# sch_Power.net
KiCad netlist of a schematic drawn in Altium Designer
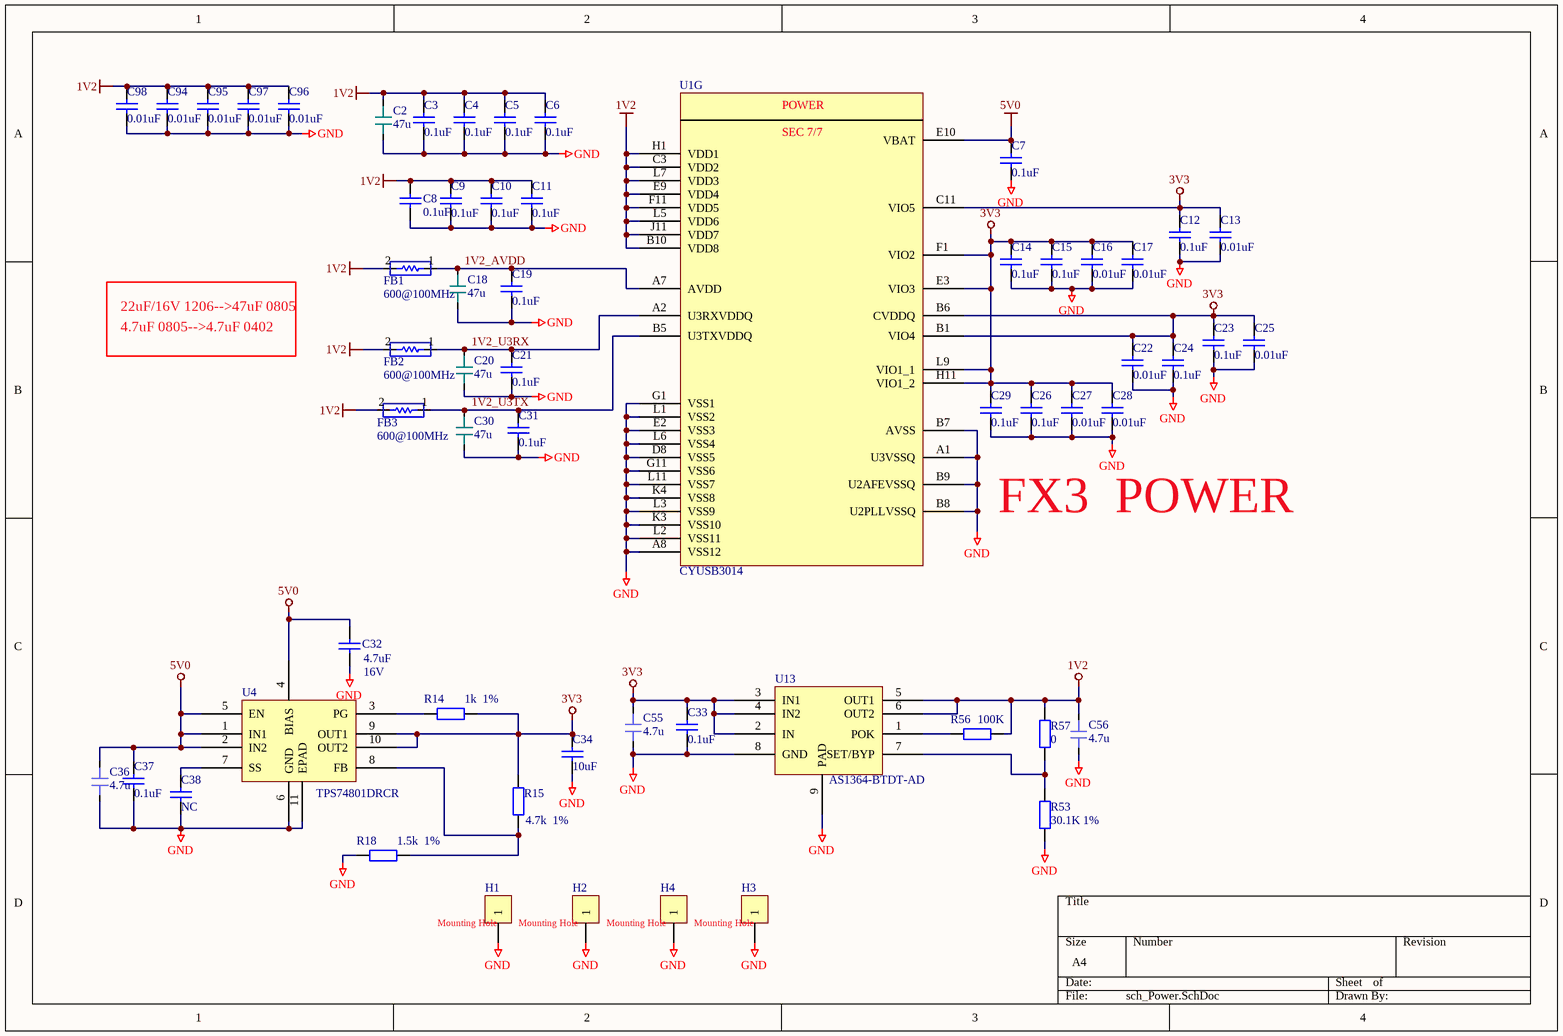
[diagram p0: sch_Power.SchDoc]

(export (version "E")
  (design (tool "Eeschema 10.0.6"))
  (components
    (comp (ref "C2")
      (value "47u")
      (footprint "0805C")
      (description "CC08052B476M5B20D")
      (libsource (lib "V0P1") (part "cap0805"))
    )
    (comp (ref "C3")
      (value "0.1uF")
      (footprint "0402C")
      (description "Capacitor")
      (fields (field (name "PUBLISHER") "Altium Limited"))
      (libsource (lib "Miscellaneous Devices") (part "Cap"))
    )
    (comp (ref "C4")
      (value "0.1uF")
      (footprint "0402C")
      (description "Capacitor")
      (fields (field (name "PUBLISHER") "Altium Limited"))
      (libsource (lib "Miscellaneous Devices") (part "Cap"))
    )
    (comp (ref "C5")
      (value "0.1uF")
      (footprint "0402C")
      (description "Capacitor")
      (fields (field (name "PUBLISHER") "Altium Limited"))
      (libsource (lib "Miscellaneous Devices") (part "Cap"))
    )
    (comp (ref "C6")
      (value "0.1uF")
      (footprint "0402C")
      (description "Capacitor")
      (fields (field (name "PUBLISHER") "Altium Limited"))
      (libsource (lib "Miscellaneous Devices") (part "Cap"))
    )
    (comp (ref "C7")
      (value "0.1uF")
      (footprint "0402C")
      (description "Capacitor")
      (fields (field (name "PUBLISHER") "Altium Limited"))
      (libsource (lib "Miscellaneous Devices") (part "Cap"))
    )
    (comp (ref "C8")
      (value "0.1uF")
      (footprint "0402C")
      (description "Capacitor")
      (fields (field (name "PUBLISHER") "Altium Limited"))
      (libsource (lib "Miscellaneous Devices") (part "Cap"))
    )
    (comp (ref "C9")
      (value "0.1uF")
      (footprint "0402C")
      (description "Capacitor")
      (fields (field (name "PUBLISHER") "Altium Limited"))
      (libsource (lib "Miscellaneous Devices") (part "Cap"))
    )
    (comp (ref "C10")
      (value "0.1uF")
      (footprint "0402C")
      (description "Capacitor")
      (fields (field (name "PUBLISHER") "Altium Limited"))
      (libsource (lib "Miscellaneous Devices") (part "Cap"))
    )
    (comp (ref "C11")
      (value "0.1uF")
      (footprint "0402C")
      (description "Capacitor")
      (fields (field (name "PUBLISHER") "Altium Limited"))
      (libsource (lib "Miscellaneous Devices") (part "Cap"))
    )
    (comp (ref "C12")
      (value "0.1uF")
      (footprint "0402C")
      (description "Capacitor")
      (fields (field (name "PUBLISHER") "Altium Limited"))
      (libsource (lib "Miscellaneous Devices") (part "Cap"))
    )
    (comp (ref "C13")
      (value "0.01uF")
      (footprint "0402C")
      (description "Capacitor")
      (fields (field (name "PUBLISHER") "Altium Limited"))
      (libsource (lib "Miscellaneous Devices") (part "Cap"))
    )
    (comp (ref "C14")
      (value "0.1uF")
      (footprint "0402C")
      (description "Capacitor")
      (fields (field (name "PUBLISHER") "Altium Limited"))
      (libsource (lib "Miscellaneous Devices") (part "Cap"))
    )
    (comp (ref "C15")
      (value "0.1uF")
      (footprint "0402C")
      (description "Capacitor")
      (fields (field (name "PUBLISHER") "Altium Limited"))
      (libsource (lib "Miscellaneous Devices") (part "Cap"))
    )
    (comp (ref "C16")
      (value "0.01uF")
      (footprint "0402C")
      (description "Capacitor")
      (fields (field (name "PUBLISHER") "Altium Limited"))
      (libsource (lib "Miscellaneous Devices") (part "Cap"))
    )
    (comp (ref "C17")
      (value "0.01uF")
      (footprint "0402C")
      (description "Capacitor")
      (fields (field (name "PUBLISHER") "Altium Limited"))
      (libsource (lib "Miscellaneous Devices") (part "Cap"))
    )
    (comp (ref "C18")
      (value "47u")
      (footprint "0805C")
      (description "CC08052B476M5B20D")
      (libsource (lib "V0P1") (part "cap0805"))
    )
    (comp (ref "C19")
      (value "0.1uF")
      (footprint "0402C")
      (description "Capacitor")
      (fields (field (name "PUBLISHER") "Altium Limited"))
      (libsource (lib "Miscellaneous Devices") (part "Cap"))
    )
    (comp (ref "C20")
      (value "47u")
      (footprint "0805C")
      (description "CC08052B476M5B20D")
      (libsource (lib "V0P1") (part "cap0805"))
    )
    (comp (ref "C21")
      (value "0.1uF")
      (footprint "0402C")
      (description "Capacitor")
      (fields (field (name "PUBLISHER") "Altium Limited"))
      (libsource (lib "Miscellaneous Devices") (part "Cap"))
    )
    (comp (ref "C22")
      (value "0.01uF")
      (footprint "0402C")
      (description "Capacitor")
      (fields (field (name "PUBLISHER") "Altium Limited"))
      (libsource (lib "Miscellaneous Devices") (part "Cap"))
    )
    (comp (ref "C23")
      (value "0.1uF")
      (footprint "0402C")
      (description "Capacitor")
      (fields (field (name "PUBLISHER") "Altium Limited"))
      (libsource (lib "Miscellaneous Devices") (part "Cap"))
    )
    (comp (ref "C24")
      (value "0.1uF")
      (footprint "0402C")
      (description "Capacitor")
      (fields (field (name "PUBLISHER") "Altium Limited"))
      (libsource (lib "Miscellaneous Devices") (part "Cap"))
    )
    (comp (ref "C25")
      (value "0.01uF")
      (footprint "0402C")
      (description "Capacitor")
      (fields (field (name "PUBLISHER") "Altium Limited"))
      (libsource (lib "Miscellaneous Devices") (part "Cap"))
    )
    (comp (ref "C26")
      (value "0.1uF")
      (footprint "0402C")
      (description "Capacitor")
      (fields (field (name "PUBLISHER") "Altium Limited"))
      (libsource (lib "Miscellaneous Devices") (part "Cap"))
    )
    (comp (ref "C27")
      (value "0.01uF")
      (footprint "0402C")
      (description "Capacitor")
      (fields (field (name "PUBLISHER") "Altium Limited"))
      (libsource (lib "Miscellaneous Devices") (part "Cap"))
    )
    (comp (ref "C28")
      (value "0.01uF")
      (footprint "0402C")
      (description "Capacitor")
      (fields (field (name "PUBLISHER") "Altium Limited"))
      (libsource (lib "Miscellaneous Devices") (part "Cap"))
    )
    (comp (ref "C29")
      (value "0.1uF")
      (footprint "0402C")
      (description "Capacitor")
      (fields (field (name "PUBLISHER") "Altium Limited"))
      (libsource (lib "Miscellaneous Devices") (part "Cap"))
    )
    (comp (ref "C30")
      (value "47u")
      (footprint "0805C")
      (description "CC08052B476M5B20D")
      (libsource (lib "V0P1") (part "cap0805"))
    )
    (comp (ref "C31")
      (value "0.1uF")
      (footprint "0402C")
      (description "Capacitor")
      (fields (field (name "PUBLISHER") "Altium Limited"))
      (libsource (lib "Miscellaneous Devices") (part "Cap"))
    )
    (comp (ref "C32")
      (value "4.7uF")
      (footprint "0805C")
      (description "Capacitor")
      (fields (field (name "ALTIUM_VALUE") "16V") (field (name "PUBLISHER") "Altium Limited"))
      (libsource (lib "Miscellaneous Devices") (part "Cap"))
    )
    (comp (ref "C33")
      (value "0.1uF")
      (footprint "0402C")
      (description "Capacitor")
      (fields (field (name "PUBLISHER") "Altium Limited"))
      (libsource (lib "Miscellaneous Devices") (part "Cap"))
    )
    (comp (ref "C34")
      (value "10uF")
      (footprint "0805C")
      (description "Capacitor")
      (fields (field (name "PUBLISHER") "Altium Limited"))
      (libsource (lib "Miscellaneous Devices") (part "Cap"))
    )
    (comp (ref "C36")
      (value "4.7u")
      (footprint "0402C")
      (description "CC0402MRX5R5BB475")
      (libsource (lib "V0P1") (part "cap0402"))
    )
    (comp (ref "C37")
      (value "0.1uF")
      (footprint "0402C")
      (description "Capacitor")
      (fields (field (name "PUBLISHER") "Altium Limited"))
      (libsource (lib "Miscellaneous Devices") (part "Cap"))
    )
    (comp (ref "C38")
      (value "NC")
      (footprint "0402C")
      (description "Capacitor")
      (fields (field (name "PUBLISHER") "Altium Limited"))
      (libsource (lib "Miscellaneous Devices") (part "Cap"))
    )
    (comp (ref "C55")
      (value "4.7u")
      (footprint "0402C")
      (description "CC0402MRX5R5BB475")
      (libsource (lib "V0P1") (part "cap0402"))
    )
    (comp (ref "C56")
      (value "4.7u")
      (footprint "0402C")
      (description "CC0402MRX5R5BB475")
      (libsource (lib "V0P1") (part "cap0402"))
    )
    (comp (ref "C94")
      (value "0.01uF")
      (footprint "0402C")
      (description "Capacitor")
      (fields (field (name "PUBLISHER") "Altium Limited"))
      (libsource (lib "Miscellaneous Devices") (part "Cap"))
    )
    (comp (ref "C95")
      (value "0.01uF")
      (footprint "0402C")
      (description "Capacitor")
      (fields (field (name "PUBLISHER") "Altium Limited"))
      (libsource (lib "Miscellaneous Devices") (part "Cap"))
    )
    (comp (ref "C96")
      (value "0.01uF")
      (footprint "0402C")
      (description "Capacitor")
      (fields (field (name "PUBLISHER") "Altium Limited"))
      (libsource (lib "Miscellaneous Devices") (part "Cap"))
    )
    (comp (ref "C97")
      (value "0.01uF")
      (footprint "0402C")
      (description "Capacitor")
      (fields (field (name "PUBLISHER") "Altium Limited"))
      (libsource (lib "Miscellaneous Devices") (part "Cap"))
    )
    (comp (ref "C98")
      (value "0.01uF")
      (footprint "0402C")
      (description "Capacitor")
      (fields (field (name "PUBLISHER") "Altium Limited"))
      (libsource (lib "Miscellaneous Devices") (part "Cap"))
    )
    (comp (ref "FB1") (value "600@100MHz") (footprint "0402R") (libsource (lib "TXW") (part "600@100MHz")))
    (comp (ref "FB2") (value "600@100MHz") (footprint "0402R") (libsource (lib "TXW") (part "600@100MHz")))
    (comp (ref "FB3") (value "600@100MHz") (footprint "0402R") (libsource (lib "TXW") (part "600@100MHz")))
    (comp (ref "H1")
      (value "CON1")
      (footprint "PAD_M3_D350_450")
      (description "Connector")
      (libsource (lib "SuperSchLib") (part "CON1"))
    )
    (comp (ref "H2")
      (value "CON1")
      (footprint "PAD_M3_D350_450")
      (description "Connector")
      (libsource (lib "SuperSchLib") (part "CON1"))
    )
    (comp (ref "H3")
      (value "CON1")
      (footprint "PAD_M3_D350_450")
      (description "Connector")
      (libsource (lib "SuperSchLib") (part "CON1"))
    )
    (comp (ref "H4")
      (value "CON1")
      (footprint "PAD_M3_D350_450")
      (description "Connector")
      (libsource (lib "SuperSchLib") (part "CON1"))
    )
    (comp (ref "R14")
      (value "1k  1%")
      (footprint "0402R")
      (description "Resistor")
      (fields (field (name "Comment") "1K") (field (name "PUBLISHER") "Altium Limited"))
      (libsource (lib "") (part "Resistor_1"))
    )
    (comp (ref "R15")
      (value "4.7k  1%")
      (footprint "0402R")
      (description "Resistor")
      (fields (field (name "Comment") "51K") (field (name "PUBLISHER") "Altium Limited"))
      (libsource (lib "SZG") (part "Resistor"))
    )
    (comp (ref "R18")
      (value "1.5k  1%")
      (footprint "0402R")
      (description "Resistor")
      (fields (field (name "Comment") "1.15K") (field (name "PUBLISHER") "Altium Limited"))
      (libsource (lib "") (part "Resistor_1"))
    )
    (comp (ref "R53")
      (value "30.1K 1%")
      (footprint "0402R")
      (description "Resistor")
      (fields (field (name "Comment") "30.1K") (field (name "PUBLISHER") "Altium Limited"))
      (libsource (lib "SZG") (part "Resistor"))
    )
    (comp (ref "R56")
      (value "100K")
      (footprint "0402R")
      (description "Resistor")
      (fields (field (name "PUBLISHER") "Altium Limited"))
      (libsource (lib "") (part "Resistor_1"))
    )
    (comp (ref "R57")
      (value "0")
      (footprint "0402R")
      (description "Resistor")
      (fields (field (name "Comment") "0R") (field (name "PUBLISHER") "Altium Limited"))
      (libsource (lib "SZG") (part "Resistor"))
    )
    (comp (ref "U1")
      (value "CYUSB3014")
      (footprint "FBGA121_P80L100W100H11")
      (libsource (lib "TXW") (part "CYUSB3014"))
    )
    (comp (ref "U4")
      (value "TPS74801DRCR")
      (footprint "SON10_P50L32W32H10_DRC")
      (libsource (lib "TXW") (part "TPS74801DRCR"))
    )
    (comp (ref "U13")
      (value "AS1364-BTDT-AD")
      (footprint "TDFN8_P65L30W30H08")
      (libsource (lib "TXW") (part "AS1364-BTDT-AD"))
    )
  )
  (nets
    (net (code "1") (name "/1V2_AVDD") (class "Default")
      (node (ref "C18") (pin "1") (pinfunction "1_1") (pintype "passive"))
      (node (ref "C19") (pin "2") (pinfunction "2_2") (pintype "passive"))
      (node (ref "FB1") (pin "1") (pinfunction "1_1") (pintype "passive"))
      (node (ref "U1") (pin "A7") (pinfunction "AVDD_A7") (pintype "passive"))
    )
    (net (code "2") (name "/1V2_U3RX") (class "Default")
      (node (ref "C20") (pin "1") (pinfunction "1_1") (pintype "passive"))
      (node (ref "C21") (pin "2") (pinfunction "2_2") (pintype "passive"))
      (node (ref "FB2") (pin "1") (pinfunction "1_1") (pintype "passive"))
      (node (ref "U1") (pin "A2") (pinfunction "U3RXVDDQ_A2") (pintype "passive"))
    )
    (net (code "3") (name "/1V2_U3TX") (class "Default")
      (node (ref "C30") (pin "1") (pinfunction "1_1") (pintype "passive"))
      (node (ref "C31") (pin "2") (pinfunction "2_2") (pintype "passive"))
      (node (ref "FB3") (pin "1") (pinfunction "1_1") (pintype "passive"))
      (node (ref "U1") (pin "B5") (pinfunction "U3TXVDDQ_B5") (pintype "passive"))
    )
    (net (code "4") (name "1V2") (class "Default")
      (node (ref "C10") (pin "2") (pinfunction "2_2") (pintype "passive"))
      (node (ref "C11") (pin "2") (pinfunction "2_2") (pintype "passive"))
      (node (ref "C2") (pin "1") (pinfunction "1_1") (pintype "passive"))
      (node (ref "C3") (pin "2") (pinfunction "2_2") (pintype "passive"))
      (node (ref "C4") (pin "2") (pinfunction "2_2") (pintype "passive"))
      (node (ref "C5") (pin "2") (pinfunction "2_2") (pintype "passive"))
      (node (ref "C56") (pin "1") (pinfunction "1_1") (pintype "passive"))
      (node (ref "C6") (pin "2") (pinfunction "2_2") (pintype "passive"))
      (node (ref "C8") (pin "2") (pinfunction "2_2") (pintype "passive"))
      (node (ref "C9") (pin "2") (pinfunction "2_2") (pintype "passive"))
      (node (ref "C94") (pin "2") (pinfunction "2_2") (pintype "passive"))
      (node (ref "C95") (pin "2") (pinfunction "2_2") (pintype "passive"))
      (node (ref "C96") (pin "2") (pinfunction "2_2") (pintype "passive"))
      (node (ref "C97") (pin "2") (pinfunction "2_2") (pintype "passive"))
      (node (ref "C98") (pin "2") (pinfunction "2_2") (pintype "passive"))
      (node (ref "FB1") (pin "2") (pinfunction "2_2") (pintype "passive"))
      (node (ref "FB2") (pin "2") (pinfunction "2_2") (pintype "passive"))
      (node (ref "FB3") (pin "2") (pinfunction "2_2") (pintype "passive"))
      (node (ref "R56") (pin "1") (pinfunction "1_1") (pintype "passive"))
      (node (ref "R57") (pin "1") (pinfunction "1_1") (pintype "passive"))
      (node (ref "U1") (pin "B10") (pinfunction "VDD8_B10") (pintype "passive"))
      (node (ref "U1") (pin "C3") (pinfunction "VDD2_C3") (pintype "passive"))
      (node (ref "U1") (pin "E9") (pinfunction "VDD4_E9") (pintype "passive"))
      (node (ref "U1") (pin "F11") (pinfunction "VDD5_F11") (pintype "passive"))
      (node (ref "U1") (pin "H1") (pinfunction "VDD1_H1") (pintype "passive"))
      (node (ref "U1") (pin "J11") (pinfunction "VDD7_J11") (pintype "passive"))
      (node (ref "U1") (pin "L5") (pinfunction "VDD6_L5") (pintype "passive"))
      (node (ref "U1") (pin "L7") (pinfunction "VDD3_L7") (pintype "passive"))
      (node (ref "U13") (pin "5") (pinfunction "OUT1_5") (pintype "passive"))
      (node (ref "U13") (pin "6") (pinfunction "OUT2_6") (pintype "passive"))
    )
    (net (code "5") (name "3V3") (class "Default")
      (node (ref "C12") (pin "2") (pinfunction "2_2") (pintype "passive"))
      (node (ref "C13") (pin "2") (pinfunction "2_2") (pintype "passive"))
      (node (ref "C14") (pin "2") (pinfunction "2_2") (pintype "passive"))
      (node (ref "C15") (pin "2") (pinfunction "2_2") (pintype "passive"))
      (node (ref "C16") (pin "2") (pinfunction "2_2") (pintype "passive"))
      (node (ref "C17") (pin "2") (pinfunction "2_2") (pintype "passive"))
      (node (ref "C22") (pin "2") (pinfunction "2_2") (pintype "passive"))
      (node (ref "C23") (pin "2") (pinfunction "2_2") (pintype "passive"))
      (node (ref "C24") (pin "2") (pinfunction "2_2") (pintype "passive"))
      (node (ref "C25") (pin "2") (pinfunction "2_2") (pintype "passive"))
      (node (ref "C26") (pin "2") (pinfunction "2_2") (pintype "passive"))
      (node (ref "C27") (pin "2") (pinfunction "2_2") (pintype "passive"))
      (node (ref "C28") (pin "2") (pinfunction "2_2") (pintype "passive"))
      (node (ref "C29") (pin "2") (pinfunction "2_2") (pintype "passive"))
      (node (ref "C33") (pin "2") (pinfunction "2_2") (pintype "passive"))
      (node (ref "C34") (pin "2") (pinfunction "2_2") (pintype "passive"))
      (node (ref "C55") (pin "1") (pinfunction "1_1") (pintype "passive"))
      (node (ref "R14") (pin "1") (pinfunction "1_1") (pintype "passive"))
      (node (ref "R15") (pin "1") (pinfunction "1_1") (pintype "passive"))
      (node (ref "U1") (pin "B1") (pinfunction "VIO4_B1") (pintype "passive"))
      (node (ref "U1") (pin "B6") (pinfunction "CVDDQ_B6") (pintype "passive"))
      (node (ref "U1") (pin "C11") (pinfunction "VIO5_C11") (pintype "power_in"))
      (node (ref "U1") (pin "E3") (pinfunction "VIO3_E3") (pintype "passive"))
      (node (ref "U1") (pin "F1") (pinfunction "VIO2_F1") (pintype "passive"))
      (node (ref "U1") (pin "H11") (pinfunction "VIO1_2_H11") (pintype "passive"))
      (node (ref "U1") (pin "L9") (pinfunction "VIO1_1_L9") (pintype "passive"))
      (node (ref "U13") (pin "2") (pinfunction "IN_2") (pintype "passive"))
      (node (ref "U13") (pin "3") (pinfunction "IN1_3") (pintype "passive"))
      (node (ref "U13") (pin "4") (pinfunction "IN2_4") (pintype "passive"))
      (node (ref "U4") (pin "10") (pinfunction "OUT2_10") (pintype "passive"))
      (node (ref "U4") (pin "9") (pinfunction "OUT1_9") (pintype "passive"))
    )
    (net (code "6") (name "5V0") (class "Default")
      (node (ref "C32") (pin "1") (pinfunction "1_1") (pintype "passive"))
      (node (ref "C36") (pin "1") (pinfunction "1_1") (pintype "passive"))
      (node (ref "C37") (pin "2") (pinfunction "2_2") (pintype "passive"))
      (node (ref "C7") (pin "2") (pinfunction "2_2") (pintype "passive"))
      (node (ref "U1") (pin "E10") (pinfunction "VBAT_E10") (pintype "passive"))
      (node (ref "U4") (pin "1") (pinfunction "IN1_1") (pintype "passive"))
      (node (ref "U4") (pin "2") (pinfunction "IN2_2") (pintype "passive"))
      (node (ref "U4") (pin "4") (pinfunction "BIAS_4") (pintype "passive"))
      (node (ref "U4") (pin "5") (pinfunction "EN_5") (pintype "passive"))
    )
    (net (code "7") (name "GND") (class "Default")
      (node (ref "C10") (pin "1") (pinfunction "1_1") (pintype "passive"))
      (node (ref "C11") (pin "1") (pinfunction "1_1") (pintype "passive"))
      (node (ref "C12") (pin "1") (pinfunction "1_1") (pintype "passive"))
      (node (ref "C13") (pin "1") (pinfunction "1_1") (pintype "passive"))
      (node (ref "C14") (pin "1") (pinfunction "1_1") (pintype "passive"))
      (node (ref "C15") (pin "1") (pinfunction "1_1") (pintype "passive"))
      (node (ref "C16") (pin "1") (pinfunction "1_1") (pintype "passive"))
      (node (ref "C17") (pin "1") (pinfunction "1_1") (pintype "passive"))
      (node (ref "C18") (pin "2") (pinfunction "2_2") (pintype "passive"))
      (node (ref "C19") (pin "1") (pinfunction "1_1") (pintype "passive"))
      (node (ref "C2") (pin "2") (pinfunction "2_2") (pintype "passive"))
      (node (ref "C20") (pin "2") (pinfunction "2_2") (pintype "passive"))
      (node (ref "C21") (pin "1") (pinfunction "1_1") (pintype "passive"))
      (node (ref "C22") (pin "1") (pinfunction "1_1") (pintype "passive"))
      (node (ref "C23") (pin "1") (pinfunction "1_1") (pintype "passive"))
      (node (ref "C24") (pin "1") (pinfunction "1_1") (pintype "passive"))
      (node (ref "C25") (pin "1") (pinfunction "1_1") (pintype "passive"))
      (node (ref "C26") (pin "1") (pinfunction "1_1") (pintype "passive"))
      (node (ref "C27") (pin "1") (pinfunction "1_1") (pintype "passive"))
      (node (ref "C28") (pin "1") (pinfunction "1_1") (pintype "passive"))
      (node (ref "C29") (pin "1") (pinfunction "1_1") (pintype "passive"))
      (node (ref "C3") (pin "1") (pinfunction "1_1") (pintype "passive"))
      (node (ref "C30") (pin "2") (pinfunction "2_2") (pintype "passive"))
      (node (ref "C31") (pin "1") (pinfunction "1_1") (pintype "passive"))
      (node (ref "C32") (pin "2") (pinfunction "2_2") (pintype "passive"))
      (node (ref "C33") (pin "1") (pinfunction "1_1") (pintype "passive"))
      (node (ref "C34") (pin "1") (pinfunction "1_1") (pintype "passive"))
      (node (ref "C36") (pin "2") (pinfunction "2_2") (pintype "passive"))
      (node (ref "C37") (pin "1") (pinfunction "1_1") (pintype "passive"))
      (node (ref "C38") (pin "1") (pinfunction "1_1") (pintype "passive"))
      (node (ref "C4") (pin "1") (pinfunction "1_1") (pintype "passive"))
      (node (ref "C5") (pin "1") (pinfunction "1_1") (pintype "passive"))
      (node (ref "C55") (pin "2") (pinfunction "2_2") (pintype "passive"))
      (node (ref "C56") (pin "2") (pinfunction "2_2") (pintype "passive"))
      (node (ref "C6") (pin "1") (pinfunction "1_1") (pintype "passive"))
      (node (ref "C7") (pin "1") (pinfunction "1_1") (pintype "passive"))
      (node (ref "C8") (pin "1") (pinfunction "1_1") (pintype "passive"))
      (node (ref "C9") (pin "1") (pinfunction "1_1") (pintype "passive"))
      (node (ref "C94") (pin "1") (pinfunction "1_1") (pintype "passive"))
      (node (ref "C95") (pin "1") (pinfunction "1_1") (pintype "passive"))
      (node (ref "C96") (pin "1") (pinfunction "1_1") (pintype "passive"))
      (node (ref "C97") (pin "1") (pinfunction "1_1") (pintype "passive"))
      (node (ref "C98") (pin "1") (pinfunction "1_1") (pintype "passive"))
      (node (ref "H1") (pin "1") (pinfunction "1_1") (pintype "passive"))
      (node (ref "H2") (pin "1") (pinfunction "1_1") (pintype "passive"))
      (node (ref "H3") (pin "1") (pinfunction "1_1") (pintype "passive"))
      (node (ref "H4") (pin "1") (pinfunction "1_1") (pintype "passive"))
      (node (ref "R18") (pin "2") (pinfunction "2_2") (pintype "passive"))
      (node (ref "R53") (pin "2") (pinfunction "2_2") (pintype "passive"))
      (node (ref "U1") (pin "A1") (pinfunction "U3VSSQ_A1") (pintype "passive"))
      (node (ref "U1") (pin "A8") (pinfunction "VSS12_A8") (pintype "passive"))
      (node (ref "U1") (pin "B7") (pinfunction "AVSS_B7") (pintype "passive"))
      (node (ref "U1") (pin "B8") (pinfunction "U2PLLVSSQ_B8") (pintype "passive"))
      (node (ref "U1") (pin "B9") (pinfunction "U2AFEVSSQ_B9") (pintype "passive"))
      (node (ref "U1") (pin "D8") (pinfunction "VSS5_D8") (pintype "passive"))
      (node (ref "U1") (pin "E2") (pinfunction "VSS3_E2") (pintype "passive"))
      (node (ref "U1") (pin "G1") (pinfunction "VSS1_G1") (pintype "passive"))
      (node (ref "U1") (pin "G11") (pinfunction "VSS6_G11") (pintype "passive"))
      (node (ref "U1") (pin "K3") (pinfunction "VSS10_K3") (pintype "passive"))
      (node (ref "U1") (pin "K4") (pinfunction "VSS8_K4") (pintype "passive"))
      (node (ref "U1") (pin "L1") (pinfunction "VSS2_L1") (pintype "passive"))
      (node (ref "U1") (pin "L11") (pinfunction "VSS7_L11") (pintype "passive"))
      (node (ref "U1") (pin "L2") (pinfunction "VSS11_L2") (pintype "passive"))
      (node (ref "U1") (pin "L3") (pinfunction "VSS9_L3") (pintype "passive"))
      (node (ref "U1") (pin "L6") (pinfunction "VSS4_L6") (pintype "passive"))
      (node (ref "U13") (pin "8") (pinfunction "GND_8") (pintype "passive"))
      (node (ref "U13") (pin "9") (pinfunction "PAD_9") (pintype "passive"))
      (node (ref "U4") (pin "11") (pinfunction "EPAD_11") (pintype "passive"))
      (node (ref "U4") (pin "6") (pinfunction "GND_6") (pintype "passive"))
    )
    (net (code "8") (name "Net-(U4-FB)") (class "Default")
      (node (ref "R15") (pin "2") (pinfunction "2_2") (pintype "passive"))
      (node (ref "R18") (pin "1") (pinfunction "1_1") (pintype "passive"))
      (node (ref "U4") (pin "8") (pinfunction "FB_8") (pintype "passive"))
    )
    (net (code "9") (name "Net-(U4-PG)") (class "Default")
      (node (ref "R14") (pin "2") (pinfunction "2_2") (pintype "passive"))
      (node (ref "U4") (pin "3") (pinfunction "PG_3") (pintype "passive"))
    )
    (net (code "10") (name "Net-(U4-SS)") (class "Default")
      (node (ref "C38") (pin "2") (pinfunction "2_2") (pintype "passive"))
      (node (ref "U4") (pin "7") (pinfunction "SS_7") (pintype "passive"))
    )
    (net (code "11") (name "Net-(U13-POK)") (class "Default")
      (node (ref "R56") (pin "2") (pinfunction "2_2") (pintype "passive"))
      (node (ref "U13") (pin "1") (pinfunction "POK_1") (pintype "passive"))
    )
    (net (code "12") (name "Net-(U13-SET{slash}BYP)") (class "Default")
      (node (ref "R53") (pin "1") (pinfunction "1_1") (pintype "passive"))
      (node (ref "R57") (pin "2") (pinfunction "2_2") (pintype "passive"))
      (node (ref "U13") (pin "7") (pinfunction "SET/BYP_7") (pintype "passive"))
    )
  )
)
